# Sheet3.net
KiCad netlist of a schematic drawn in Altium Designer
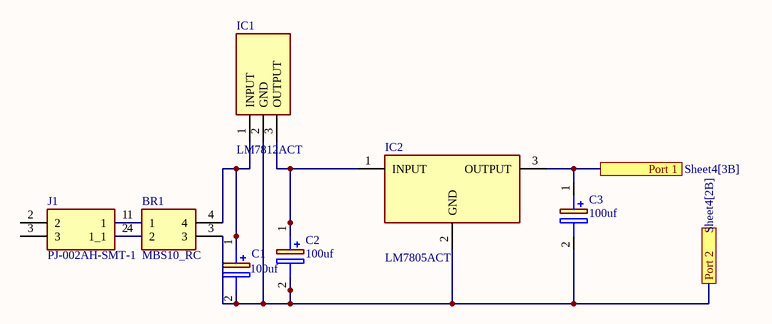
[diagram p0: Sheet3.SchDoc]

(export (version "E")
  (design (tool "Eeschema 10.0.6"))
  (components
    (comp (ref "BR1")
      (value "MBS10_RC")
      (footprint "SamacSys:SOP240P690X290-4N")
      (description "Bridge Rectifier")
      (fields (field (name "MANUFACTURER_PART_NUMBER") "MBS10 RC"))
      (libsource (lib "*") (part "MBS10_RC"))
    )
    (comp (ref "C1")
      (value "100uf")
      (footprint "SamacSys:CAPPRD500W65D1250H2700")
      (description "Capacitor Polarised")
      (fields (field (name "MANUFACTURER_PART_NUMBER") "EEUTA1E102LB"))
      (libsource (lib "*") (part "EEUTA1E102LB"))
    )
    (comp (ref "C2")
      (value "100uf")
      (footprint "SamacSys:CAPPRD500W65D1250H2700")
      (description "Capacitor Polarised")
      (fields (field (name "MANUFACTURER_PART_NUMBER") "EEUTA1E102LB"))
      (libsource (lib "*") (part "EEUTA1E102LB"))
    )
    (comp (ref "C3")
      (value "100uf")
      (footprint "SamacSys:CAPPRD500W65D1250H2700")
      (description "Capacitor Polarised")
      (fields (field (name "MANUFACTURER_PART_NUMBER") "EEUTA1E102LB"))
      (libsource (lib "*") (part "EEUTA1E102LB"))
    )
    (comp (ref "IC1")
      (value "LM7812ACT")
      (footprint "SamacSys:TO254P470X1016X2019-3P")
      (description "Integrated Circuit")
      (fields (field (name "MOUSER PART NUMBER") "512-LM7812ACT"))
      (libsource (lib "SamacSys") (part "LM7812ACT"))
    )
    (comp (ref "IC2")
      (value "LM7805ACT")
      (footprint "SamacSys:TO254P470X1016X2019-3P")
      (description "Integrated Circuit")
      (fields (field (name "MOUSER PART NUMBER") "512-LM7805ACT"))
      (libsource (lib "*") (part "LM7805ACT"))
    )
    (comp (ref "J1")
      (value "PJ-002AH-SMT-1")
      (footprint "SamacSys:PJ002AHSMT1")
      (description "Connector")
      (libsource (lib "*") (part "PJ-002AH-SMT-1"))
    )
  )
  (nets
    (net (code "1") (name "/Port 1") (class "Default")
      (node (ref "C3") (pin "1") (pinfunction "+_1") (pintype "passive"))
      (node (ref "IC2") (pin "3") (pinfunction "OUTPUT_3") (pintype "passive"))
    )
    (net (code "2") (name "/Port 2") (class "Default")
      (node (ref "BR1") (pin "3") (pinfunction "3_3") (pintype "passive"))
      (node (ref "C1") (pin "2") (pinfunction "-_2") (pintype "passive"))
      (node (ref "C2") (pin "2") (pinfunction "-_2") (pintype "passive"))
      (node (ref "C3") (pin "2") (pinfunction "-_2") (pintype "passive"))
      (node (ref "IC1") (pin "2") (pinfunction "GND_2") (pintype "passive"))
      (node (ref "IC2") (pin "2") (pinfunction "GND_2") (pintype "passive"))
    )
    (net (code "3") (name "Net-(BR1-Pad1)") (class "Default")
      (node (ref "BR1") (pin "1") (pinfunction "1_1") (pintype "passive"))
      (node (ref "J1") (pin "1") (pinfunction "1_1") (pintype "passive"))
    )
    (net (code "4") (name "Net-(C1-+)") (class "Default")
      (node (ref "BR1") (pin "4") (pinfunction "4_4") (pintype "passive"))
      (node (ref "C1") (pin "1") (pinfunction "+_1") (pintype "passive"))
      (node (ref "IC1") (pin "1") (pinfunction "INPUT_1") (pintype "passive"))
    )
    (net (code "5") (name "Net-(C2-+)") (class "Default")
      (node (ref "C2") (pin "1") (pinfunction "+_1") (pintype "passive"))
      (node (ref "IC1") (pin "3") (pinfunction "OUTPUT_3") (pintype "passive"))
      (node (ref "IC2") (pin "1") (pinfunction "INPUT_1") (pintype "passive"))
    )
    (net (code "6") (name "Net-(J1-1_1)") (class "Default")
      (node (ref "BR1") (pin "2") (pinfunction "2_2") (pintype "passive"))
      (node (ref "J1") (pin "4") (pinfunction "1_1_4") (pintype "passive"))
    )
    (net (code "7") (name "unconnected-(J1-Pad2)") (class "Default")
      (node (ref "J1") (pin "2") (pinfunction "2_2") (pintype "passive"))
    )
    (net (code "8") (name "unconnected-(J1-Pad3)") (class "Default")
      (node (ref "J1") (pin "3") (pinfunction "3_3") (pintype "passive"))
    )
  )
)
